# 02_power_supply.net
KiCad netlist of a schematic drawn in Altium Designer
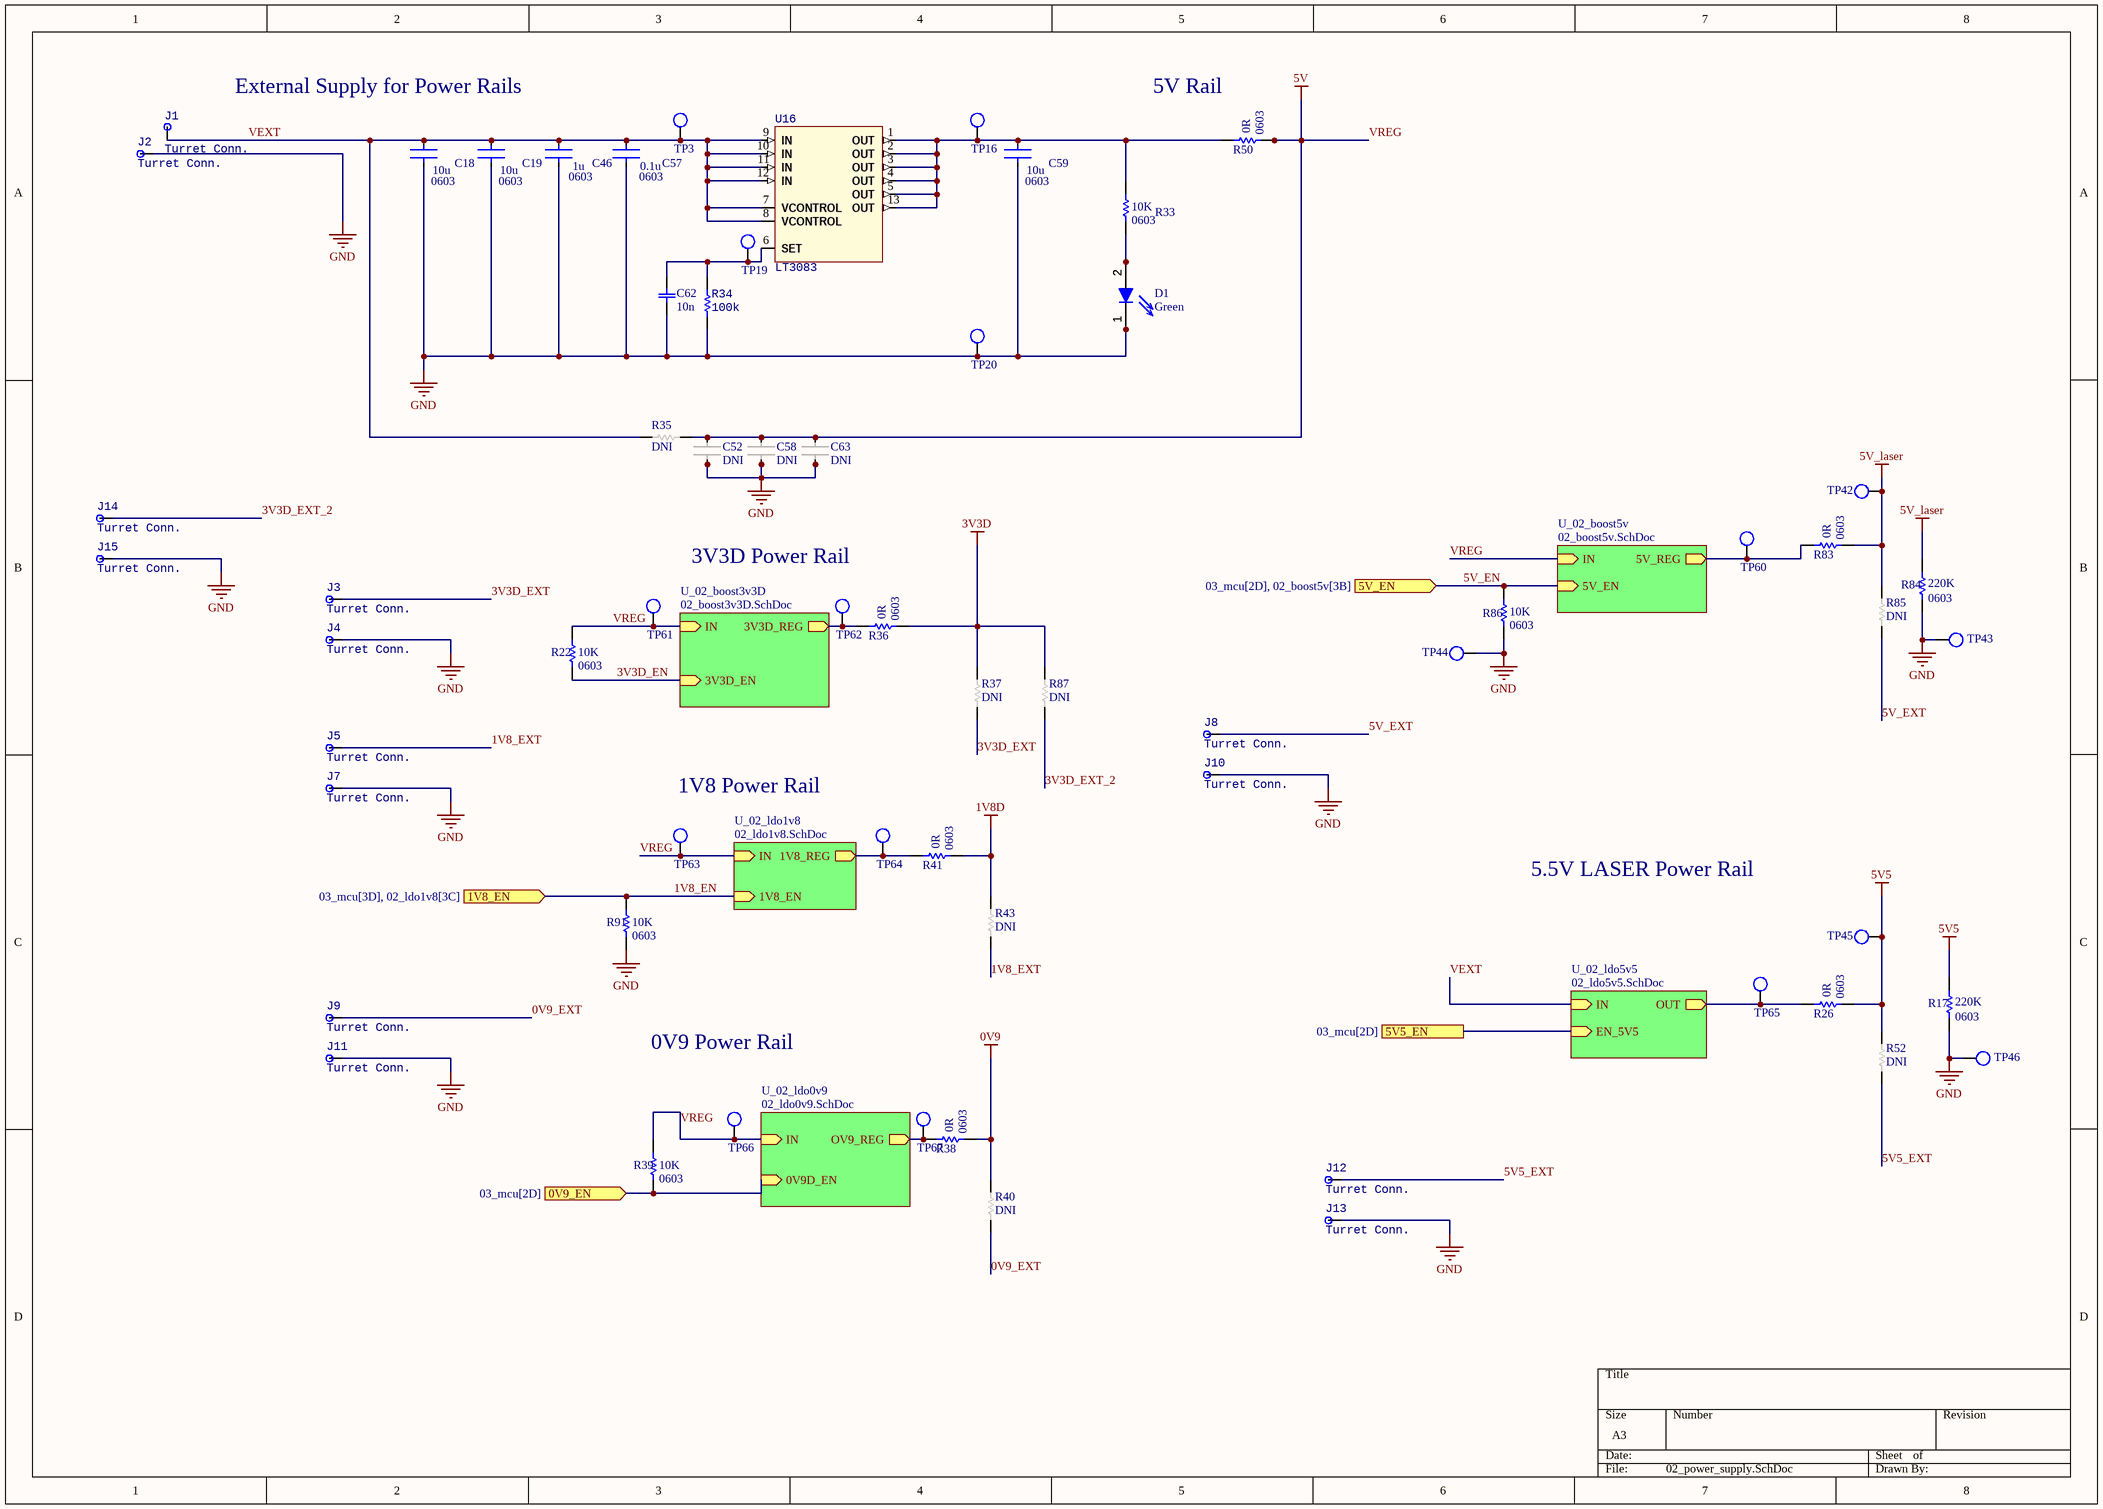
[diagram p0: 02_power_supply.SchDoc]

(export (version "E")
  (design (tool "Eeschema 10.0.6"))
  (components
    (comp (ref "C18")
      (value "C1608X5R1A106K080AC")
      (footprint "CAPTDK0603")
      (description "CAP CER 10UF 10V X5R 0603")
      (libsource (lib "tcspc00") (part "C1608X5R1A106K080AC"))
    )
    (comp (ref "C19")
      (value "C1608X5R1A106K080AC")
      (footprint "CAPTDK0603")
      (description "CAP CER 10UF 10V X5R 0603")
      (libsource (lib "tcspc00") (part "C1608X5R1A106K080AC"))
    )
    (comp (ref "C46")
      (value "C1608X5R1E105K080AC")
      (footprint "CAPTDK0603")
      (description "CAP CER 1UF 25V X5R 0603")
      (libsource (lib "tcspc00") (part "C1608X5R1E105K080AC"))
    )
    (comp (ref "C52")
      (value "DNI")
      (footprint "CAPTDK0603")
      (description "CAP PROVISION 0603")
      (libsource (lib "tcspc00") (part "C0402_PROVISION"))
    )
    (comp (ref "C57")
      (value "CGA3E2X7R1H104K080AA")
      (footprint "CAPTDK0603")
      (description "CAP CER 0.1UF 50V X7R 0603")
      (libsource (lib "tcspc00") (part "CGA3E2X7R1H104K080AA"))
    )
    (comp (ref "C58")
      (value "DNI")
      (footprint "CAPTDK0603")
      (description "CAP PROVISION 0603")
      (libsource (lib "tcspc00") (part "C0402_PROVISION"))
    )
    (comp (ref "C59")
      (value "C1608X5R1A106K080AC")
      (footprint "CAPTDK0603")
      (description "CAP CER 10UF 10V X5R 0603")
      (libsource (lib "tcspc00") (part "C1608X5R1A106K080AC"))
    )
    (comp (ref "C62")
      (value "10n")
      (footprint "CAP_CL10")
      (description "CAP CER 10NF 50V X7R 0603")
      (fields
        (field (name "MANUFACTURER") "Yageo")
        (field (name "MANUFACTURER PART NUMBER") "CC0603KRX7R9BB103")
      )
      (libsource (lib "tcspc00") (part "CC0603KRX7R9BB103"))
    )
    (comp (ref "C63")
      (value "DNI")
      (footprint "CAPTDK0603")
      (description "CAP PROVISION 0603")
      (libsource (lib "tcspc00") (part "C0402_PROVISION"))
    )
    (comp (ref "D1")
      (value "Green")
      (footprint "DISPLAY-LED")
      (description "LED GREEN CLEAR 0603  SMD")
      (libsource (lib "tcspc00") (part "LTST-C191KGKT"))
    )
    (comp (ref "J1")
      (value "Turret Conn.")
      (footprint "2501-X")
      (description "TERM TURRET SINGLE L=5.56MM TIN")
      (fields
        (field (name "MANUFACTURER") "Mill-Max")
        (field (name "MANUFACTURER PART NUMBER") "2501-2-00-80-00-00-07-0")
      )
      (libsource (lib "tcspc00") (part "2501-2-00-80-00-00-07-0"))
    )
    (comp (ref "J2")
      (value "Turret Conn.")
      (footprint "2501-X")
      (description "TERM TURRET SINGLE L=5.56MM TIN")
      (fields
        (field (name "MANUFACTURER") "Mill-Max")
        (field (name "MANUFACTURER PART NUMBER") "2501-2-00-80-00-00-07-0")
      )
      (libsource (lib "tcspc00") (part "2501-2-00-80-00-00-07-0"))
    )
    (comp (ref "J3")
      (value "Turret Conn.")
      (footprint "2501-X")
      (description "TERM TURRET SINGLE L=5.56MM TIN")
      (fields
        (field (name "MANUFACTURER") "Mill-Max")
        (field (name "MANUFACTURER PART NUMBER") "2501-2-00-80-00-00-07-0")
      )
      (libsource (lib "tcspc00") (part "2501-2-00-80-00-00-07-0"))
    )
    (comp (ref "J4")
      (value "Turret Conn.")
      (footprint "2501-X")
      (description "TERM TURRET SINGLE L=5.56MM TIN")
      (fields
        (field (name "MANUFACTURER") "Mill-Max")
        (field (name "MANUFACTURER PART NUMBER") "2501-2-00-80-00-00-07-0")
      )
      (libsource (lib "tcspc00") (part "2501-2-00-80-00-00-07-0"))
    )
    (comp (ref "J5")
      (value "Turret Conn.")
      (footprint "2501-X")
      (description "TERM TURRET SINGLE L=5.56MM TIN")
      (fields
        (field (name "MANUFACTURER") "Mill-Max")
        (field (name "MANUFACTURER PART NUMBER") "2501-2-00-80-00-00-07-0")
      )
      (libsource (lib "tcspc00") (part "2501-2-00-80-00-00-07-0"))
    )
    (comp (ref "J7")
      (value "Turret Conn.")
      (footprint "2501-X")
      (description "TERM TURRET SINGLE L=5.56MM TIN")
      (fields
        (field (name "MANUFACTURER") "Mill-Max")
        (field (name "MANUFACTURER PART NUMBER") "2501-2-00-80-00-00-07-0")
      )
      (libsource (lib "tcspc00") (part "2501-2-00-80-00-00-07-0"))
    )
    (comp (ref "J8")
      (value "Turret Conn.")
      (footprint "2501-X")
      (description "TERM TURRET SINGLE L=5.56MM TIN")
      (fields
        (field (name "MANUFACTURER") "Mill-Max")
        (field (name "MANUFACTURER PART NUMBER") "2501-2-00-80-00-00-07-0")
      )
      (libsource (lib "tcspc00") (part "2501-2-00-80-00-00-07-0"))
    )
    (comp (ref "J9")
      (value "Turret Conn.")
      (footprint "2501-X")
      (description "TERM TURRET SINGLE L=5.56MM TIN")
      (fields
        (field (name "MANUFACTURER") "Mill-Max")
        (field (name "MANUFACTURER PART NUMBER") "2501-2-00-80-00-00-07-0")
      )
      (libsource (lib "tcspc00") (part "2501-2-00-80-00-00-07-0"))
    )
    (comp (ref "J10")
      (value "Turret Conn.")
      (footprint "2501-X")
      (description "TERM TURRET SINGLE L=5.56MM TIN")
      (fields
        (field (name "MANUFACTURER") "Mill-Max")
        (field (name "MANUFACTURER PART NUMBER") "2501-2-00-80-00-00-07-0")
      )
      (libsource (lib "tcspc00") (part "2501-2-00-80-00-00-07-0"))
    )
    (comp (ref "J11")
      (value "Turret Conn.")
      (footprint "2501-X")
      (description "TERM TURRET SINGLE L=5.56MM TIN")
      (fields
        (field (name "MANUFACTURER") "Mill-Max")
        (field (name "MANUFACTURER PART NUMBER") "2501-2-00-80-00-00-07-0")
      )
      (libsource (lib "tcspc00") (part "2501-2-00-80-00-00-07-0"))
    )
    (comp (ref "J12")
      (value "Turret Conn.")
      (footprint "2501-X")
      (description "TERM TURRET SINGLE L=5.56MM TIN")
      (fields
        (field (name "MANUFACTURER") "Mill-Max")
        (field (name "MANUFACTURER PART NUMBER") "2501-2-00-80-00-00-07-0")
      )
      (libsource (lib "tcspc00") (part "2501-2-00-80-00-00-07-0"))
    )
    (comp (ref "J13")
      (value "Turret Conn.")
      (footprint "2501-X")
      (description "TERM TURRET SINGLE L=5.56MM TIN")
      (fields
        (field (name "MANUFACTURER") "Mill-Max")
        (field (name "MANUFACTURER PART NUMBER") "2501-2-00-80-00-00-07-0")
      )
      (libsource (lib "tcspc00") (part "2501-2-00-80-00-00-07-0"))
    )
    (comp (ref "J14")
      (value "Turret Conn.")
      (footprint "2501-X")
      (description "TERM TURRET SINGLE L=5.56MM TIN")
      (fields
        (field (name "MANUFACTURER") "Mill-Max")
        (field (name "MANUFACTURER PART NUMBER") "2501-2-00-80-00-00-07-0")
      )
      (libsource (lib "tcspc00") (part "2501-2-00-80-00-00-07-0"))
    )
    (comp (ref "J15")
      (value "Turret Conn.")
      (footprint "2501-X")
      (description "TERM TURRET SINGLE L=5.56MM TIN")
      (fields
        (field (name "MANUFACTURER") "Mill-Max")
        (field (name "MANUFACTURER PART NUMBER") "2501-2-00-80-00-00-07-0")
      )
      (libsource (lib "tcspc00") (part "2501-2-00-80-00-00-07-0"))
    )
    (comp (ref "R17")
      (value "RMCF0603FT220K")
      (footprint "RES-STACK-POLE-0603")
      (description "RES 220K OHM 1% 1/10W 0603")
      (libsource (lib "tcspc00") (part "RMCF0603FT220K"))
    )
    (comp (ref "R22")
      (value "RMCF0603JG10K0")
      (footprint "RES-STACK-POLE-0603")
      (description "RES 10K OHM 5% 1/10W 0603")
      (libsource (lib "tcspc00") (part "RMCF0603JG10K0"))
    )
    (comp (ref "R26")
      (value "RMCF0603ZT0R00")
      (footprint "RES-STACK-POLE-0603")
      (description "RES 0 OHM JUMPER 1/10W 0603")
      (libsource (lib "tcspc00") (part "RMCF0603ZT0R00"))
    )
    (comp (ref "R33")
      (value "RMCF0603JG10K0")
      (footprint "RES-STACK-POLE-0603")
      (description "RES 10K OHM 5% 1/10W 0603")
      (libsource (lib "tcspc00") (part "RMCF0603JG10K0"))
    )
    (comp (ref "R34")
      (value "100k")
      (footprint "RES_0603")
      (description "RES 100K OHM 1% 1/10W 0603")
      (fields
        (field (name "MANUFACTURER") "Stackpole Electronics")
        (field (name "MANUFACTURER PART NUMBER") "RMCF0603FT100K")
      )
      (libsource (lib "tcspc00") (part "RMCF0603FT100K_1"))
    )
    (comp (ref "R35")
      (value "DNI")
      (footprint "RES_0603")
      (description "RES DNI 0603")
      (libsource (lib "tcspc00") (part "R0603"))
    )
    (comp (ref "R36")
      (value "RMCF0603ZT0R00")
      (footprint "RES-STACK-POLE-0603")
      (description "RES 0 OHM JUMPER 1/10W 0603")
      (libsource (lib "tcspc00") (part "RMCF0603ZT0R00"))
    )
    (comp (ref "R37")
      (value "DNI")
      (footprint "RES_0603")
      (description "RES DNI 0603")
      (libsource (lib "tcspc00") (part "R0603"))
    )
    (comp (ref "R38")
      (value "RMCF0603ZT0R00")
      (footprint "RES-STACK-POLE-0603")
      (description "RES 0 OHM JUMPER 1/10W 0603")
      (libsource (lib "tcspc00") (part "RMCF0603ZT0R00"))
    )
    (comp (ref "R39")
      (value "RMCF0603JG10K0")
      (footprint "RES-STACK-POLE-0603")
      (description "RES 10K OHM 5% 1/10W 0603")
      (libsource (lib "tcspc00") (part "RMCF0603JG10K0"))
    )
    (comp (ref "R40")
      (value "DNI")
      (footprint "RES_0603")
      (description "RES DNI 0603")
      (libsource (lib "tcspc00") (part "R0603"))
    )
    (comp (ref "R41")
      (value "RMCF0603ZT0R00")
      (footprint "RES-STACK-POLE-0603")
      (description "RES 0 OHM JUMPER 1/10W 0603")
      (libsource (lib "tcspc00") (part "RMCF0603ZT0R00"))
    )
    (comp (ref "R43")
      (value "DNI")
      (footprint "RES_0603")
      (description "RES DNI 0603")
      (libsource (lib "tcspc00") (part "R0603"))
    )
    (comp (ref "R50")
      (value "RMCF0603ZT0R00")
      (footprint "RES-STACK-POLE-0603")
      (description "RES 0 OHM JUMPER 1/10W 0603")
      (libsource (lib "tcspc00") (part "RMCF0603ZT0R00"))
    )
    (comp (ref "R52")
      (value "DNI")
      (footprint "RES_0603")
      (description "RES DNI 0603")
      (libsource (lib "tcspc00") (part "R0603"))
    )
    (comp (ref "R83")
      (value "RMCF0603ZT0R00")
      (footprint "RES-STACK-POLE-0603")
      (description "RES 0 OHM JUMPER 1/10W 0603")
      (libsource (lib "tcspc00") (part "RMCF0603ZT0R00"))
    )
    (comp (ref "R84")
      (value "RMCF0603FT220K")
      (footprint "RES-STACK-POLE-0603")
      (description "RES 220K OHM 1% 1/10W 0603")
      (libsource (lib "tcspc00") (part "RMCF0603FT220K"))
    )
    (comp (ref "R85")
      (value "DNI")
      (footprint "RES_0603")
      (description "RES DNI 0603")
      (libsource (lib "tcspc00") (part "R0603"))
    )
    (comp (ref "R86")
      (value "RMCF0603JG10K0")
      (footprint "RES-STACK-POLE-0603")
      (description "RES 10K OHM 5% 1/10W 0603")
      (libsource (lib "tcspc00") (part "RMCF0603JG10K0"))
    )
    (comp (ref "R87")
      (value "DNI")
      (footprint "RES_0603")
      (description "RES DNI 0603")
      (libsource (lib "tcspc00") (part "R0603"))
    )
    (comp (ref "R91")
      (value "RMCF0603JG10K0")
      (footprint "RES-STACK-POLE-0603")
      (description "RES 10K OHM 5% 1/10W 0603")
      (libsource (lib "tcspc00") (part "RMCF0603JG10K0"))
    )
    (comp (ref "TP3")
      (value "TESTPOINT_S")
      (footprint "TESTPOINT_S")
      (description "Testpoint Surface Pad")
      (libsource (lib "tcspc00") (part "TESTPOINT_S"))
    )
    (comp (ref "TP16")
      (value "TESTPOINT_S")
      (footprint "TESTPOINT_S")
      (description "Testpoint Surface Pad")
      (libsource (lib "tcspc00") (part "TESTPOINT_S"))
    )
    (comp (ref "TP19")
      (value "TESTPOINT_S")
      (footprint "TESTPOINT_S")
      (description "Testpoint Surface Pad")
      (libsource (lib "tcspc00") (part "TESTPOINT_S"))
    )
    (comp (ref "TP20")
      (value "TESTPOINT_S")
      (footprint "TESTPOINT_S")
      (description "Testpoint Surface Pad")
      (libsource (lib "tcspc00") (part "TESTPOINT_S"))
    )
    (comp (ref "TP42")
      (value "TESTPOINT_S")
      (footprint "TESTPOINT_S")
      (description "Testpoint Surface Pad")
      (libsource (lib "tcspc00") (part "TESTPOINT_S"))
    )
    (comp (ref "TP43")
      (value "TESTPOINT_S")
      (footprint "TESTPOINT_S")
      (description "Testpoint Surface Pad")
      (libsource (lib "tcspc00") (part "TESTPOINT_S"))
    )
    (comp (ref "TP44")
      (value "TESTPOINT_S")
      (footprint "TESTPOINT_S")
      (description "Testpoint Surface Pad")
      (libsource (lib "tcspc00") (part "TESTPOINT_S"))
    )
    (comp (ref "TP45")
      (value "TESTPOINT_S")
      (footprint "TESTPOINT_S")
      (description "Testpoint Surface Pad")
      (libsource (lib "tcspc00") (part "TESTPOINT_S"))
    )
    (comp (ref "TP46")
      (value "TESTPOINT_S")
      (footprint "TESTPOINT_S")
      (description "Testpoint Surface Pad")
      (libsource (lib "tcspc00") (part "TESTPOINT_S"))
    )
    (comp (ref "TP60")
      (value "TESTPOINT_S")
      (footprint "TESTPOINT_S")
      (description "Testpoint Surface Pad")
      (libsource (lib "tcspc00") (part "TESTPOINT_S"))
    )
    (comp (ref "TP61")
      (value "TESTPOINT_S")
      (footprint "TESTPOINT_S")
      (description "Testpoint Surface Pad")
      (libsource (lib "tcspc00") (part "TESTPOINT_S"))
    )
    (comp (ref "TP62")
      (value "TESTPOINT_S")
      (footprint "TESTPOINT_S")
      (description "Testpoint Surface Pad")
      (libsource (lib "tcspc00") (part "TESTPOINT_S"))
    )
    (comp (ref "TP63")
      (value "TESTPOINT_S")
      (footprint "TESTPOINT_S")
      (description "Testpoint Surface Pad")
      (libsource (lib "tcspc00") (part "TESTPOINT_S"))
    )
    (comp (ref "TP64")
      (value "TESTPOINT_S")
      (footprint "TESTPOINT_S")
      (description "Testpoint Surface Pad")
      (libsource (lib "tcspc00") (part "TESTPOINT_S"))
    )
    (comp (ref "TP65")
      (value "TESTPOINT_S")
      (footprint "TESTPOINT_S")
      (description "Testpoint Surface Pad")
      (libsource (lib "tcspc00") (part "TESTPOINT_S"))
    )
    (comp (ref "TP66")
      (value "TESTPOINT_S")
      (footprint "TESTPOINT_S")
      (description "Testpoint Surface Pad")
      (libsource (lib "tcspc00") (part "TESTPOINT_S"))
    )
    (comp (ref "TP67")
      (value "TESTPOINT_S")
      (footprint "TESTPOINT_S")
      (description "Testpoint Surface Pad")
      (libsource (lib "tcspc00") (part "TESTPOINT_S"))
    )
    (comp (ref "U16")
      (value "LT3083")
      (footprint "DF-12_LT3083")
      (description "IC REG LINEAR POS ADJ 3A 12DFN")
      (libsource (lib "tcspc00") (part "LT3083EDF#PBF"))
    )
  )
  (nets
    (net (code "1") (name "/0V9_EN") (class "Default")
      (node (ref "R39") (pin "1") (pinfunction "1_1") (pintype "passive"))
    )
    (net (code "2") (name "/0V9_EXT") (class "Default")
      (node (ref "J9") (pin "1") (pinfunction "1_1") (pintype "power_in"))
      (node (ref "R40") (pin "2") (pinfunction "2_2") (pintype "passive"))
    )
    (net (code "3") (name "/1V8_EN") (class "Default")
      (node (ref "R91") (pin "2") (pinfunction "2_2") (pintype "passive"))
    )
    (net (code "4") (name "/1V8_EXT") (class "Default")
      (node (ref "J5") (pin "1") (pinfunction "1_1") (pintype "power_in"))
      (node (ref "R43") (pin "2") (pinfunction "2_2") (pintype "passive"))
    )
    (net (code "5") (name "/1V8_REG") (class "Default")
      (node (ref "R41") (pin "2") (pinfunction "2_2") (pintype "passive"))
      (node (ref "TP64") (pin "1") (pinfunction "1_1") (pintype "passive"))
    )
    (net (code "6") (name "/3V3D_EN") (class "Default")
      (node (ref "R22") (pin "1") (pinfunction "1_1") (pintype "passive"))
    )
    (net (code "7") (name "/3V3D_EXT") (class "Default")
      (node (ref "J3") (pin "1") (pinfunction "1_1") (pintype "power_in"))
      (node (ref "R37") (pin "2") (pinfunction "2_2") (pintype "passive"))
    )
    (net (code "8") (name "/3V3D_EXT_2") (class "Default")
      (node (ref "J14") (pin "1") (pinfunction "1_1") (pintype "power_in"))
      (node (ref "R87") (pin "2") (pinfunction "2_2") (pintype "passive"))
    )
    (net (code "9") (name "/3V3D_REG") (class "Default")
      (node (ref "R36") (pin "2") (pinfunction "2_2") (pintype "passive"))
      (node (ref "TP62") (pin "1") (pinfunction "1_1") (pintype "passive"))
    )
    (net (code "11") (name "/5V5_EXT") (class "Default")
      (node (ref "J12") (pin "1") (pinfunction "1_1") (pintype "power_in"))
      (node (ref "R52") (pin "2") (pinfunction "2_2") (pintype "passive"))
    )
    (net (code "12") (name "/5V_EN") (class "Default")
      (node (ref "R86") (pin "2") (pinfunction "2_2") (pintype "passive"))
    )
    (net (code "13") (name "/5V_EXT") (class "Default")
      (node (ref "J8") (pin "1") (pinfunction "1_1") (pintype "power_in"))
      (node (ref "R85") (pin "2") (pinfunction "2_2") (pintype "passive"))
    )
    (net (code "14") (name "/5V_REG") (class "Default")
      (node (ref "R83") (pin "2") (pinfunction "2_2") (pintype "passive"))
      (node (ref "TP60") (pin "1") (pinfunction "1_1") (pintype "passive"))
    )
    (net (code "15") (name "/OUT") (class "Default")
      (node (ref "R26") (pin "2") (pinfunction "2_2") (pintype "passive"))
      (node (ref "TP65") (pin "1") (pinfunction "1_1") (pintype "passive"))
    )
    (net (code "16") (name "/OV9_REG") (class "Default")
      (node (ref "R38") (pin "2") (pinfunction "2_2") (pintype "passive"))
      (node (ref "TP67") (pin "1") (pinfunction "1_1") (pintype "passive"))
    )
    (net (code "17") (name "/VEXT") (class "Default")
      (node (ref "C18") (pin "1") (pinfunction "1_1") (pintype "passive"))
      (node (ref "C19") (pin "1") (pinfunction "1_1") (pintype "passive"))
      (node (ref "C46") (pin "1") (pinfunction "1_1") (pintype "passive"))
      (node (ref "C57") (pin "1") (pinfunction "1_1") (pintype "passive"))
      (node (ref "J1") (pin "1") (pinfunction "1_1") (pintype "power_in"))
      (node (ref "R35") (pin "1") (pinfunction "1_1") (pintype "passive"))
      (node (ref "TP3") (pin "1") (pinfunction "1_1") (pintype "passive"))
      (node (ref "U16") (pin "10") (pinfunction "IN_10") (pintype "input"))
      (node (ref "U16") (pin "11") (pinfunction "IN_11") (pintype "input"))
      (node (ref "U16") (pin "12") (pinfunction "IN_12") (pintype "input"))
      (node (ref "U16") (pin "7") (pinfunction "VCONTROL_7") (pintype "power_in"))
      (node (ref "U16") (pin "8") (pinfunction "VCONTROL_8") (pintype "power_in"))
      (node (ref "U16") (pin "9") (pinfunction "IN_9") (pintype "input"))
    )
    (net (code "18") (name "0V9") (class "Default")
      (node (ref "R38") (pin "1") (pinfunction "1_1") (pintype "passive"))
      (node (ref "R40") (pin "1") (pinfunction "1_1") (pintype "passive"))
    )
    (net (code "19") (name "1V8D") (class "Default")
      (node (ref "R41") (pin "1") (pinfunction "1_1") (pintype "passive"))
      (node (ref "R43") (pin "1") (pinfunction "1_1") (pintype "passive"))
    )
    (net (code "20") (name "3V3D") (class "Default")
      (node (ref "R36") (pin "1") (pinfunction "1_1") (pintype "passive"))
      (node (ref "R37") (pin "1") (pinfunction "1_1") (pintype "passive"))
      (node (ref "R87") (pin "1") (pinfunction "1_1") (pintype "passive"))
    )
    (net (code "21") (name "5V") (class "Default")
      (node (ref "C52") (pin "1") (pinfunction "1_1") (pintype "passive"))
      (node (ref "C58") (pin "1") (pinfunction "1_1") (pintype "passive"))
      (node (ref "C63") (pin "1") (pinfunction "1_1") (pintype "passive"))
      (node (ref "R22") (pin "2") (pinfunction "2_2") (pintype "passive"))
      (node (ref "R35") (pin "2") (pinfunction "2_2") (pintype "passive"))
      (node (ref "R39") (pin "2") (pinfunction "2_2") (pintype "passive"))
      (node (ref "R50") (pin "1") (pinfunction "1_1") (pintype "passive"))
      (node (ref "TP61") (pin "1") (pinfunction "1_1") (pintype "passive"))
      (node (ref "TP63") (pin "1") (pinfunction "1_1") (pintype "passive"))
      (node (ref "TP66") (pin "1") (pinfunction "1_1") (pintype "passive"))
    )
    (net (code "22") (name "5V5") (class "Default")
      (node (ref "R17") (pin "2") (pinfunction "2_2") (pintype "passive"))
      (node (ref "R26") (pin "1") (pinfunction "1_1") (pintype "passive"))
      (node (ref "R52") (pin "1") (pinfunction "1_1") (pintype "passive"))
      (node (ref "TP45") (pin "1") (pinfunction "1_1") (pintype "passive"))
    )
    (net (code "23") (name "5V_laser") (class "Default")
      (node (ref "R83") (pin "1") (pinfunction "1_1") (pintype "passive"))
      (node (ref "R84") (pin "2") (pinfunction "2_2") (pintype "passive"))
      (node (ref "R85") (pin "1") (pinfunction "1_1") (pintype "passive"))
      (node (ref "TP42") (pin "1") (pinfunction "1_1") (pintype "passive"))
    )
    (net (code "24") (name "GND") (class "Default")
      (node (ref "C18") (pin "2") (pinfunction "2_2") (pintype "passive"))
      (node (ref "C19") (pin "2") (pinfunction "2_2") (pintype "passive"))
      (node (ref "C46") (pin "2") (pinfunction "2_2") (pintype "passive"))
      (node (ref "C52") (pin "2") (pinfunction "2_2") (pintype "passive"))
      (node (ref "C57") (pin "2") (pinfunction "2_2") (pintype "passive"))
      (node (ref "C58") (pin "2") (pinfunction "2_2") (pintype "passive"))
      (node (ref "C59") (pin "2") (pinfunction "2_2") (pintype "passive"))
      (node (ref "C62") (pin "1") (pinfunction "1_1") (pintype "passive"))
      (node (ref "C63") (pin "2") (pinfunction "2_2") (pintype "passive"))
      (node (ref "D1") (pin "1") (pintype "passive"))
      (node (ref "J10") (pin "1") (pinfunction "1_1") (pintype "power_in"))
      (node (ref "J11") (pin "1") (pinfunction "1_1") (pintype "power_in"))
      (node (ref "J13") (pin "1") (pinfunction "1_1") (pintype "power_in"))
      (node (ref "J15") (pin "1") (pinfunction "1_1") (pintype "power_in"))
      (node (ref "J2") (pin "1") (pinfunction "1_1") (pintype "power_in"))
      (node (ref "J4") (pin "1") (pinfunction "1_1") (pintype "power_in"))
      (node (ref "J7") (pin "1") (pinfunction "1_1") (pintype "power_in"))
      (node (ref "R17") (pin "1") (pinfunction "1_1") (pintype "passive"))
      (node (ref "R34") (pin "1") (pinfunction "1_1") (pintype "passive"))
      (node (ref "R84") (pin "1") (pinfunction "1_1") (pintype "passive"))
      (node (ref "R86") (pin "1") (pinfunction "1_1") (pintype "passive"))
      (node (ref "R91") (pin "1") (pinfunction "1_1") (pintype "passive"))
      (node (ref "TP20") (pin "1") (pinfunction "1_1") (pintype "passive"))
      (node (ref "TP43") (pin "1") (pinfunction "1_1") (pintype "passive"))
      (node (ref "TP44") (pin "1") (pinfunction "1_1") (pintype "passive"))
      (node (ref "TP46") (pin "1") (pinfunction "1_1") (pintype "passive"))
    )
    (net (code "25") (name "Net-(C59-Pad1)") (class "Default")
      (node (ref "C59") (pin "1") (pinfunction "1_1") (pintype "passive"))
      (node (ref "R33") (pin "2") (pinfunction "2_2") (pintype "passive"))
      (node (ref "R50") (pin "2") (pinfunction "2_2") (pintype "passive"))
      (node (ref "TP16") (pin "1") (pinfunction "1_1") (pintype "passive"))
      (node (ref "U16") (pin "1") (pinfunction "OUT_1") (pintype "output"))
      (node (ref "U16") (pin "13") (pinfunction "OUT_13") (pintype "output"))
      (node (ref "U16") (pin "2") (pinfunction "OUT_2") (pintype "output"))
      (node (ref "U16") (pin "3") (pinfunction "OUT_3") (pintype "output"))
      (node (ref "U16") (pin "4") (pinfunction "OUT_4") (pintype "output"))
      (node (ref "U16") (pin "5") (pinfunction "OUT_5") (pintype "output"))
    )
    (net (code "26") (name "Net-(D1-Pad2)") (class "Default")
      (node (ref "D1") (pin "2") (pintype "passive"))
      (node (ref "R33") (pin "1") (pinfunction "1_1") (pintype "passive"))
    )
    (net (code "27") (name "Net-(U16-SET)") (class "Default")
      (node (ref "C62") (pin "2") (pinfunction "2_2") (pintype "passive"))
      (node (ref "R34") (pin "2") (pinfunction "2_2") (pintype "passive"))
      (node (ref "TP19") (pin "1") (pinfunction "1_1") (pintype "passive"))
      (node (ref "U16") (pin "6") (pinfunction "SET_6") (pintype "passive"))
    )
  )
)
